# CE_BJTInfineonSOT343_Simple_v2.net
KiCad netlist of a schematic drawn in Altium Designer
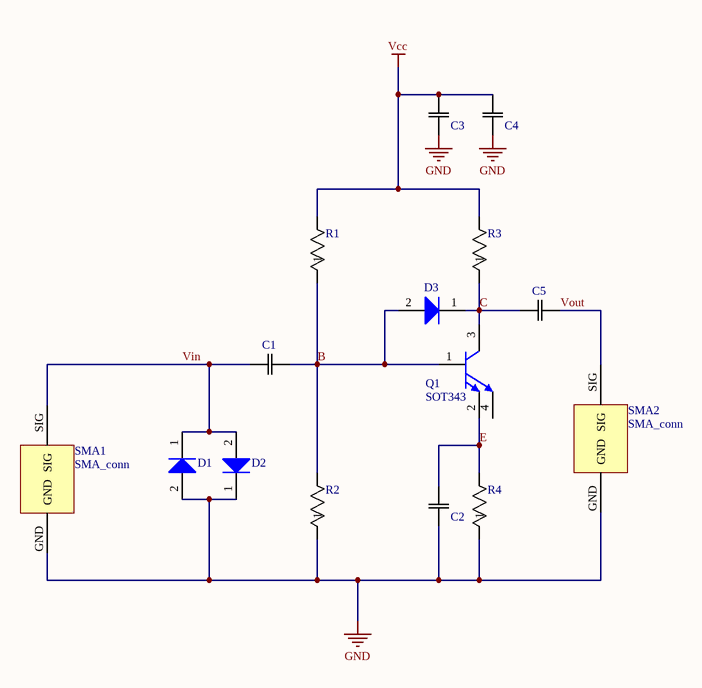
[diagram p0: CE_BJTInfineonSOT343_Simple_v2.SchDoc]

(export (version "E")
  (design (tool "Eeschema 10.0.6"))
  (components
    (comp (ref "C1")
      (value "Part Number: ECH-U1C182GX5")
      (footprint "CAP_K1")
      (description "No Description Available")
      (fields
        (field (name "MANUFACTURER_PART_NUMBER") "ECH-U1C182GX5")
        (field (name "COPYRIGHT") "Copyright (C) 2018 Accelerated Designs. All rights reserved")
      )
      (libsource (lib "0603Capacitor") (part "ECH-U1C182GX5"))
    )
    (comp (ref "C2")
      (value "Part Number: ECH-U1C182GX5")
      (footprint "CAP_K1")
      (description "No Description Available")
      (fields
        (field (name "MANUFACTURER_PART_NUMBER") "ECH-U1C182GX5")
        (field (name "COPYRIGHT") "Copyright (C) 2018 Accelerated Designs. All rights reserved")
      )
      (libsource (lib "0603Capacitor") (part "ECH-U1C182GX5"))
    )
    (comp (ref "C3")
      (value "Part Number: ECH-U1C182GX5")
      (footprint "CAP_K1")
      (description "No Description Available")
      (fields
        (field (name "MANUFACTURER_PART_NUMBER") "ECH-U1C182GX5")
        (field (name "COPYRIGHT") "Copyright (C) 2018 Accelerated Designs. All rights reserved")
      )
      (libsource (lib "0603Capacitor") (part "ECH-U1C182GX5"))
    )
    (comp (ref "C4")
      (value "Part Number: ECH-U1C182GX5")
      (footprint "CAP_K1")
      (description "No Description Available")
      (fields
        (field (name "MANUFACTURER_PART_NUMBER") "ECH-U1C182GX5")
        (field (name "COPYRIGHT") "Copyright (C) 2018 Accelerated Designs. All rights reserved")
      )
      (libsource (lib "0603Capacitor") (part "ECH-U1C182GX5"))
    )
    (comp (ref "C5")
      (value "Part Number: ECH-U1C182GX5")
      (footprint "CAP_K1")
      (description "No Description Available")
      (fields
        (field (name "MANUFACTURER_PART_NUMBER") "ECH-U1C182GX5")
        (field (name "COPYRIGHT") "Copyright (C) 2018 Accelerated Designs. All rights reserved")
      )
      (libsource (lib "0603Capacitor") (part "ECH-U1C182GX5"))
    )
    (comp (ref "D1")
      (value "~")
      (footprint "INF-SOD323_V")
      (description "Single Silicon Schottky Diode, 110 mA IF Max, SOD32, Green")
      (fields (field (name "MANUFACTURER") "Infineon") (field (name "PARTNUMBER") "BAT15-03W"))
      (libsource (lib "Infineon_RFSchottkyDiode_SOD323") (part "BAT15-03W"))
    )
    (comp (ref "D2")
      (value "~")
      (footprint "INF-SOD323_V")
      (description "Single Silicon Schottky Diode, 110 mA IF Max, SOD32, Green")
      (fields (field (name "MANUFACTURER") "Infineon") (field (name "PARTNUMBER") "BAT15-03W"))
      (libsource (lib "Infineon_RFSchottkyDiode_SOD323") (part "BAT15-03W"))
    )
    (comp (ref "D3")
      (value "~")
      (footprint "INF-SOD323_V")
      (description "Single Silicon Schottky Diode, 110 mA IF Max, SOD32, Green")
      (fields (field (name "MANUFACTURER") "Infineon") (field (name "PARTNUMBER") "BAT15-03W"))
      (libsource (lib "Infineon_RFSchottkyDiode_SOD323") (part "BAT15-03W"))
    )
    (comp (ref "Q1")
      (value "SOT343")
      (footprint "INF-SOT343_V")
      (fields (field (name "MANUFACTURER") "Infineon") (field (name "PARTNUMBER") "BFP840ESD"))
      (libsource (lib "Infineon_RFBJT_SOT343") (part "BFP840ESD"))
    )
    (comp (ref "R1")
      (value "~")
      (footprint "RES_RC0201_P6XP3")
      (description "No Description Available")
      (fields
        (field (name "MANUFACTURER_PART_NUMBER") "RC0201FR-0718KL")
        (field (name "COPYRIGHT") "Copyright (C) 2018 Accelerated Designs. All rights reserved")
      )
      (libsource (lib "0201Resistor_Yageo") (part "RC0201FR-0718KL"))
    )
    (comp (ref "R2")
      (value "~")
      (footprint "RES_RC0201_P6XP3")
      (description "No Description Available")
      (fields
        (field (name "MANUFACTURER_PART_NUMBER") "RC0201FR-0718KL")
        (field (name "COPYRIGHT") "Copyright (C) 2018 Accelerated Designs. All rights reserved")
      )
      (libsource (lib "0201Resistor_Yageo") (part "RC0201FR-0718KL"))
    )
    (comp (ref "R3")
      (value "~")
      (footprint "RES_RC0201_P6XP3")
      (description "No Description Available")
      (fields
        (field (name "MANUFACTURER_PART_NUMBER") "RC0201FR-0718KL")
        (field (name "COPYRIGHT") "Copyright (C) 2018 Accelerated Designs. All rights reserved")
      )
      (libsource (lib "0201Resistor_Yageo") (part "RC0201FR-0718KL"))
    )
    (comp (ref "R4")
      (value "~")
      (footprint "RES_RC0201_P6XP3")
      (description "No Description Available")
      (fields
        (field (name "MANUFACTURER_PART_NUMBER") "RC0201FR-0718KL")
        (field (name "COPYRIGHT") "Copyright (C) 2018 Accelerated Designs. All rights reserved")
      )
      (libsource (lib "0201Resistor_Yageo") (part "RC0201FR-0718KL"))
    )
    (comp (ref "SMA1")
      (value "SMA_conn")
      (footprint "SMA_conn")
      (libsource (lib "SMA_conn") (part "SMA_conn"))
    )
    (comp (ref "SMA2")
      (value "SMA_conn")
      (footprint "SMA_conn")
      (libsource (lib "SMA_conn") (part "SMA_conn"))
    )
  )
  (nets
    (net (code "1") (name "/B") (class "Default")
      (node (ref "C1") (pin "2") (pinfunction "2_2") (pintype "passive"))
      (node (ref "D3") (pin "2") (pinfunction "A_2") (pintype "passive"))
      (node (ref "Q1") (pin "1") (pinfunction "B_1") (pintype "passive"))
      (node (ref "R1") (pin "1") (pinfunction "1_1") (pintype "passive"))
      (node (ref "R2") (pin "2") (pinfunction "2_2") (pintype "passive"))
    )
    (net (code "2") (name "/C") (class "Default")
      (node (ref "C5") (pin "1") (pinfunction "1_1") (pintype "passive"))
      (node (ref "D3") (pin "1") (pinfunction "K_1") (pintype "passive"))
      (node (ref "Q1") (pin "3") (pinfunction "C_3") (pintype "passive"))
      (node (ref "R3") (pin "1") (pinfunction "1_1") (pintype "passive"))
    )
    (net (code "3") (name "/E") (class "Default")
      (node (ref "C2") (pin "2") (pinfunction "2_2") (pintype "passive"))
      (node (ref "Q1") (pin "2") (pinfunction "E_2") (pintype "passive"))
      (node (ref "R4") (pin "2") (pinfunction "2_2") (pintype "passive"))
    )
    (net (code "4") (name "/Vin") (class "Default")
      (node (ref "C1") (pin "1") (pinfunction "1_1") (pintype "passive"))
      (node (ref "D1") (pin "1") (pinfunction "K_1") (pintype "passive"))
      (node (ref "D2") (pin "2") (pinfunction "A_2") (pintype "passive"))
      (node (ref "SMA1") (pin "SIG") (pinfunction "SIG_SIG") (pintype "passive"))
    )
    (net (code "5") (name "/Vout") (class "Default")
      (node (ref "C5") (pin "2") (pinfunction "2_2") (pintype "passive"))
      (node (ref "SMA2") (pin "SIG") (pinfunction "SIG_SIG") (pintype "passive"))
    )
    (net (code "6") (name "GND") (class "Default")
      (node (ref "C2") (pin "1") (pinfunction "1_1") (pintype "passive"))
      (node (ref "C3") (pin "1") (pinfunction "1_1") (pintype "passive"))
      (node (ref "C4") (pin "1") (pinfunction "1_1") (pintype "passive"))
      (node (ref "D1") (pin "2") (pinfunction "A_2") (pintype "passive"))
      (node (ref "D2") (pin "1") (pinfunction "K_1") (pintype "passive"))
      (node (ref "R2") (pin "1") (pinfunction "1_1") (pintype "passive"))
      (node (ref "R4") (pin "1") (pinfunction "1_1") (pintype "passive"))
      (node (ref "SMA1") (pin "GND") (pinfunction "GND_GND") (pintype "passive"))
      (node (ref "SMA2") (pin "GND") (pinfunction "GND_GND") (pintype "passive"))
    )
    (net (code "7") (name "Vcc") (class "Default")
      (node (ref "C3") (pin "2") (pinfunction "2_2") (pintype "passive"))
      (node (ref "C4") (pin "2") (pinfunction "2_2") (pintype "passive"))
      (node (ref "R1") (pin "2") (pinfunction "2_2") (pintype "passive"))
      (node (ref "R3") (pin "2") (pinfunction "2_2") (pintype "passive"))
    )
    (net (code "8") (name "unconnected-(Q1-E-Pad4)") (class "Default")
      (node (ref "Q1") (pin "4") (pinfunction "E_4") (pintype "passive"))
    )
  )
)
